# schema_wemosD1-chata.net
KiCad netlist of a schematic drawn in EAGLE
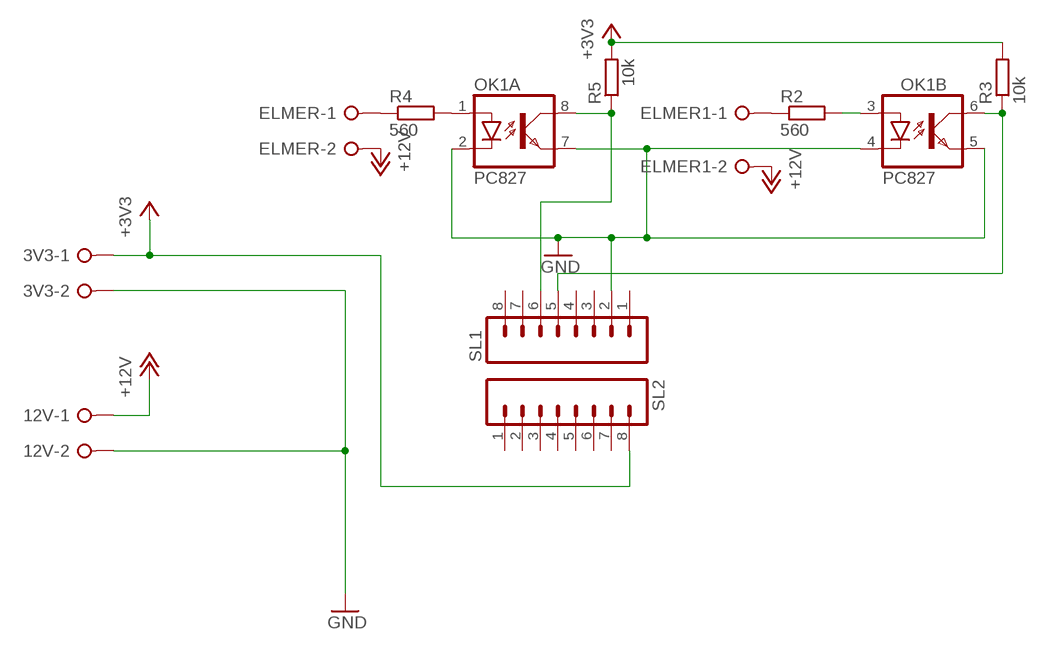
[diagram p0: schematic, sheet 1]

(export (version "E")
  (design (tool "Eeschema 10.0.6"))
  (components
    (comp (ref "3V3")
      (value "W237-02P")
      (footprint "eagle-import:W237-132")
      (libsource (lib "eagle-import") (part "W237-02P"))
    )
    (comp (ref "12V")
      (value "W237-02P")
      (footprint "eagle-import:W237-132")
      (libsource (lib "eagle-import") (part "W237-02P"))
    )
    (comp (ref "ELMER")
      (value "W237-02P")
      (footprint "eagle-import:W237-132")
      (libsource (lib "eagle-import") (part "W237-02P"))
    )
    (comp (ref "ELMER1")
      (value "W237-02P")
      (footprint "eagle-import:W237-132")
      (libsource (lib "eagle-import") (part "W237-02P"))
    )
    (comp (ref "OK1")
      (value "PC827")
      (footprint "eagle-import:DIL08")
      (libsource (lib "eagle-import") (part "PC827"))
    )
    (comp (ref "R2")
      (value "560")
      (footprint "eagle-import:0204_7")
      (libsource (lib "eagle-import") (part "R-EU_0204/7"))
    )
    (comp (ref "R3")
      (value "10k")
      (footprint "eagle-import:0204_7")
      (libsource (lib "eagle-import") (part "R-EU_0204/7"))
    )
    (comp (ref "R4")
      (value "560")
      (footprint "eagle-import:0204_7")
      (libsource (lib "eagle-import") (part "R-EU_0204/7"))
    )
    (comp (ref "R5")
      (value "10k")
      (footprint "eagle-import:0204_7")
      (libsource (lib "eagle-import") (part "R-EU_0204/7"))
    )
    (comp (ref "SL1")
      (value "M08")
      (footprint "eagle-import:08P")
      (libsource (lib "eagle-import") (part "M08"))
    )
    (comp (ref "SL2")
      (value "M08")
      (footprint "eagle-import:08P")
      (libsource (lib "eagle-import") (part "M08"))
    )
  )
  (nets
    (net (code "1") (name "+3V3") (class "Default")
      (node (ref "3V3") (pin "1") (pinfunction "KL_1") (pintype "passive"))
      (node (ref "R3") (pin "2") (pinfunction "2_2") (pintype "passive"))
      (node (ref "R5") (pin "2") (pinfunction "2_2") (pintype "passive"))
      (node (ref "SL2") (pin "8") (pinfunction "8_8") (pintype "passive"))
    )
    (net (code "2") (name "+12V") (class "Default")
      (node (ref "12V") (pin "1") (pinfunction "KL_1") (pintype "passive"))
      (node (ref "ELMER") (pin "2") (pinfunction "KL_2") (pintype "passive"))
      (node (ref "ELMER1") (pin "2") (pinfunction "KL_2") (pintype "passive"))
    )
    (net (code "3") (name "GND") (class "Default")
      (node (ref "12V") (pin "2") (pinfunction "KL_2") (pintype "passive"))
      (node (ref "3V3") (pin "2") (pinfunction "KL_2") (pintype "passive"))
      (node (ref "OK1") (pin "2") (pinfunction "C_2") (pintype "passive"))
      (node (ref "OK1") (pin "4") (pinfunction "C_4") (pintype "passive"))
      (node (ref "OK1") (pin "5") (pinfunction "EMIT_5") (pintype "passive"))
      (node (ref "OK1") (pin "7") (pinfunction "EMIT_7") (pintype "passive"))
      (node (ref "SL1") (pin "2") (pinfunction "2_2") (pintype "passive"))
    )
    (net (code "4") (name "Net-(ELMER1A-KL)") (class "Default")
      (node (ref "ELMER1") (pin "1") (pinfunction "KL_1") (pintype "passive"))
      (node (ref "R2") (pin "1") (pinfunction "1_1") (pintype "passive"))
    )
    (net (code "5") (name "Net-(ELMERA-KL)") (class "Default")
      (node (ref "ELMER") (pin "1") (pinfunction "KL_1") (pintype "passive"))
      (node (ref "R4") (pin "1") (pinfunction "1_1") (pintype "passive"))
    )
    (net (code "6") (name "Net-(OK1A-A)") (class "Default")
      (node (ref "OK1") (pin "1") (pinfunction "A_1") (pintype "passive"))
      (node (ref "R4") (pin "2") (pinfunction "2_2") (pintype "passive"))
    )
    (net (code "7") (name "Net-(OK1A-COL)") (class "Default")
      (node (ref "OK1") (pin "8") (pinfunction "COL_8") (pintype "passive"))
      (node (ref "R5") (pin "1") (pinfunction "1_1") (pintype "passive"))
      (node (ref "SL1") (pin "6") (pinfunction "6_6") (pintype "passive"))
    )
    (net (code "8") (name "Net-(OK1B-A)") (class "Default")
      (node (ref "OK1") (pin "3") (pinfunction "A_3") (pintype "passive"))
      (node (ref "R2") (pin "2") (pinfunction "2_2") (pintype "passive"))
    )
    (net (code "9") (name "Net-(OK1B-COL)") (class "Default")
      (node (ref "OK1") (pin "6") (pinfunction "COL_6") (pintype "passive"))
      (node (ref "R3") (pin "1") (pinfunction "1_1") (pintype "passive"))
      (node (ref "SL1") (pin "5") (pinfunction "5_5") (pintype "passive"))
    )
    (net (code "10") (name "unconnected-(SL1-Pad1)") (class "Default")
      (node (ref "SL1") (pin "1") (pinfunction "1_1") (pintype "passive"))
    )
    (net (code "11") (name "unconnected-(SL1-Pad3)") (class "Default")
      (node (ref "SL1") (pin "3") (pinfunction "3_3") (pintype "passive"))
    )
    (net (code "12") (name "unconnected-(SL1-Pad4)") (class "Default")
      (node (ref "SL1") (pin "4") (pinfunction "4_4") (pintype "passive"))
    )
    (net (code "13") (name "unconnected-(SL1-Pad7)") (class "Default")
      (node (ref "SL1") (pin "7") (pinfunction "7_7") (pintype "passive"))
    )
    (net (code "14") (name "unconnected-(SL1-Pad8)") (class "Default")
      (node (ref "SL1") (pin "8") (pinfunction "8_8") (pintype "passive"))
    )
    (net (code "15") (name "unconnected-(SL2-Pad1)") (class "Default")
      (node (ref "SL2") (pin "1") (pinfunction "1_1") (pintype "passive"))
    )
    (net (code "16") (name "unconnected-(SL2-Pad2)") (class "Default")
      (node (ref "SL2") (pin "2") (pinfunction "2_2") (pintype "passive"))
    )
    (net (code "17") (name "unconnected-(SL2-Pad3)") (class "Default")
      (node (ref "SL2") (pin "3") (pinfunction "3_3") (pintype "passive"))
    )
    (net (code "18") (name "unconnected-(SL2-Pad4)") (class "Default")
      (node (ref "SL2") (pin "4") (pinfunction "4_4") (pintype "passive"))
    )
    (net (code "19") (name "unconnected-(SL2-Pad5)") (class "Default")
      (node (ref "SL2") (pin "5") (pinfunction "5_5") (pintype "passive"))
    )
    (net (code "20") (name "unconnected-(SL2-Pad6)") (class "Default")
      (node (ref "SL2") (pin "6") (pinfunction "6_6") (pintype "passive"))
    )
    (net (code "21") (name "unconnected-(SL2-Pad7)") (class "Default")
      (node (ref "SL2") (pin "7") (pinfunction "7_7") (pintype "passive"))
    )
  )
)
